# FM349readerV01.net
KiCad netlist of a schematic drawn in Altium Designer
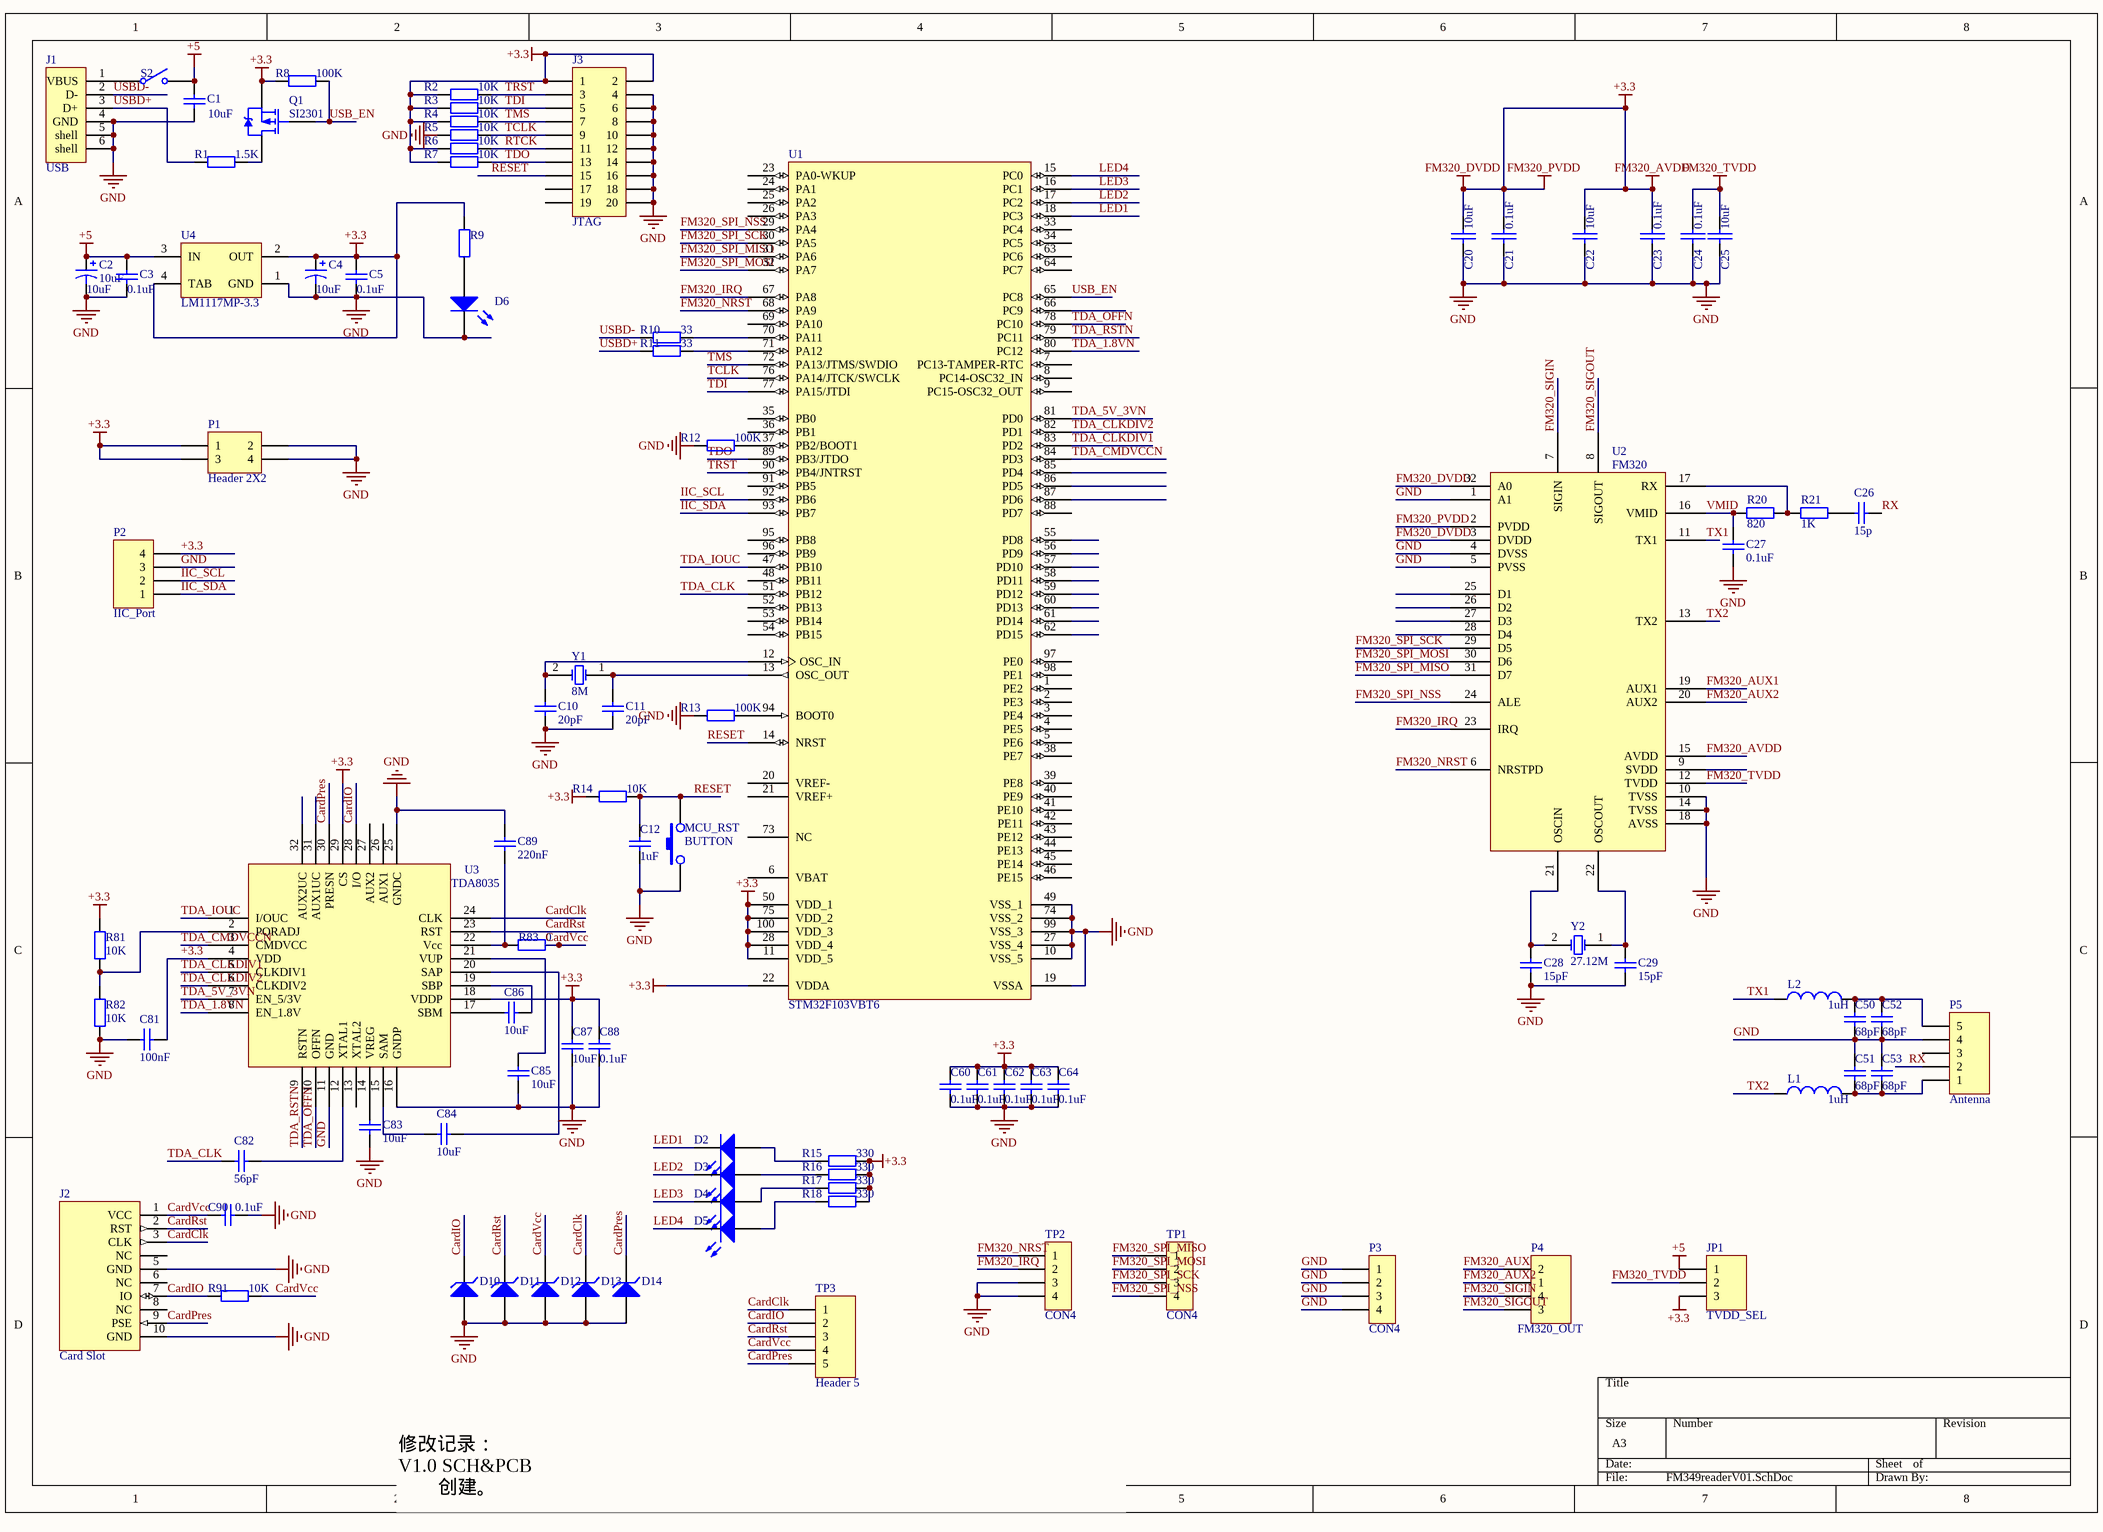
[diagram p0: FM349readerV01.SchDoc]

(export (version "E")
  (design (tool "Eeschema 10.0.6"))
  (components
    (comp (ref "C1")
      (value "10uF")
      (footprint "0805")
      (description "Capacitor")
      (libsource (lib "Miscellaneous Devices") (part "Cap"))
    )
    (comp (ref "C2")
      (value "10uF")
      (footprint "0805")
      (description "Polarized Capacitor (Radial)")
      (fields (field (name "ALTIUM_VALUE") "10uF"))
      (libsource (lib "Miscellaneous Devices") (part "Cap Pol1"))
    )
    (comp (ref "C3")
      (value "0.1uF")
      (footprint "0805")
      (description "Capacitor")
      (libsource (lib "Miscellaneous Devices") (part "Cap"))
    )
    (comp (ref "C4")
      (value "10uF")
      (footprint "0805")
      (description "Polarized Capacitor (Radial)")
      (libsource (lib "Miscellaneous Devices") (part "Cap Pol1"))
    )
    (comp (ref "C5")
      (value "0.1uF")
      (footprint "0805")
      (description "Capacitor")
      (libsource (lib "Miscellaneous Devices") (part "Cap"))
    )
    (comp (ref "C10")
      (value "20pF")
      (footprint "0805")
      (description "Capacitor")
      (libsource (lib "Miscellaneous Devices") (part "Cap"))
    )
    (comp (ref "C11")
      (value "20pF")
      (footprint "0805")
      (description "Capacitor")
      (libsource (lib "Miscellaneous Devices") (part "Cap"))
    )
    (comp (ref "C12")
      (value "1uF")
      (footprint "0805")
      (description "Capacitor")
      (libsource (lib "Miscellaneous Devices") (part "Cap"))
    )
    (comp (ref "C20")
      (value "10uF")
      (footprint "0805")
      (description "Capacitor")
      (libsource (lib "SCH_LIB") (part "CAP"))
    )
    (comp (ref "C21")
      (value "0.1uF")
      (footprint "0805")
      (description "Capacitor")
      (libsource (lib "SCH_LIB") (part "CAP"))
    )
    (comp (ref "C22")
      (value "10uF")
      (footprint "0805")
      (description "Capacitor")
      (libsource (lib "SCH_LIB") (part "CAP"))
    )
    (comp (ref "C23")
      (value "0.1uF")
      (footprint "0805")
      (description "Capacitor")
      (libsource (lib "SCH_LIB") (part "CAP"))
    )
    (comp (ref "C24")
      (value "0.1uF")
      (footprint "0805")
      (description "Capacitor")
      (libsource (lib "SCH_LIB") (part "CAP"))
    )
    (comp (ref "C25")
      (value "10uF")
      (footprint "0805")
      (description "Capacitor")
      (libsource (lib "SCH_LIB") (part "CAP"))
    )
    (comp (ref "C26")
      (value "15p")
      (footprint "0805")
      (description "Capacitor")
      (fields (field (name "Comment") "0.1uF"))
      (libsource (lib "Miscellaneous Devices") (part "Cap"))
    )
    (comp (ref "C27")
      (value "0.1uF")
      (footprint "0805")
      (description "Capacitor")
      (libsource (lib "Miscellaneous Devices") (part "Cap"))
    )
    (comp (ref "C28")
      (value "15pF")
      (footprint "0805")
      (description "Capacitor")
      (libsource (lib "Miscellaneous Devices") (part "Cap"))
    )
    (comp (ref "C29")
      (value "15pF")
      (footprint "0805")
      (description "Capacitor")
      (libsource (lib "Miscellaneous Devices") (part "Cap"))
    )
    (comp (ref "C50")
      (value "68pF")
      (footprint "0805")
      (description "Capacitor")
      (libsource (lib "Miscellaneous Devices") (part "Cap"))
    )
    (comp (ref "C51")
      (value "68pF")
      (footprint "0805")
      (description "Capacitor")
      (libsource (lib "Miscellaneous Devices") (part "Cap"))
    )
    (comp (ref "C52")
      (value "68pF")
      (footprint "0805")
      (description "Capacitor")
      (libsource (lib "Miscellaneous Devices") (part "Cap"))
    )
    (comp (ref "C53")
      (value "68pF")
      (footprint "0805")
      (description "Capacitor")
      (libsource (lib "Miscellaneous Devices") (part "Cap"))
    )
    (comp (ref "C60")
      (value "0.1uF")
      (footprint "0805")
      (description "Capacitor")
      (libsource (lib "Miscellaneous Devices") (part "Cap"))
    )
    (comp (ref "C61")
      (value "0.1uF")
      (footprint "0805")
      (description "Capacitor")
      (libsource (lib "Miscellaneous Devices") (part "Cap"))
    )
    (comp (ref "C62")
      (value "0.1uF")
      (footprint "0805")
      (description "Capacitor")
      (libsource (lib "Miscellaneous Devices") (part "Cap"))
    )
    (comp (ref "C63")
      (value "0.1uF")
      (footprint "0805")
      (description "Capacitor")
      (libsource (lib "Miscellaneous Devices") (part "Cap"))
    )
    (comp (ref "C64")
      (value "0.1uF")
      (footprint "0805")
      (description "Capacitor")
      (libsource (lib "Miscellaneous Devices") (part "Cap"))
    )
    (comp (ref "C81")
      (value "100nF")
      (footprint "0805")
      (description "Capacitor")
      (fields (field (name "Comment") "0.1uF"))
      (libsource (lib "Miscellaneous Devices") (part "Cap"))
    )
    (comp (ref "C82")
      (value "56pF")
      (footprint "0805")
      (description "Capacitor")
      (fields (field (name "Comment") "0.1uF"))
      (libsource (lib "Miscellaneous Devices") (part "Cap"))
    )
    (comp (ref "C83")
      (value "10uF")
      (footprint "0805")
      (description "Capacitor")
      (fields (field (name "Comment") "0.1uF"))
      (libsource (lib "Miscellaneous Devices") (part "Cap"))
    )
    (comp (ref "C84")
      (value "10uF")
      (footprint "0805")
      (description "Capacitor")
      (fields (field (name "Comment") "0.1uF"))
      (libsource (lib "Miscellaneous Devices") (part "Cap"))
    )
    (comp (ref "C85")
      (value "10uF")
      (footprint "0805")
      (description "Capacitor")
      (fields (field (name "Comment") "0.1uF"))
      (libsource (lib "Miscellaneous Devices") (part "Cap"))
    )
    (comp (ref "C86")
      (value "10uF")
      (footprint "0805")
      (description "Capacitor")
      (fields (field (name "Comment") "0.1uF"))
      (libsource (lib "Miscellaneous Devices") (part "Cap"))
    )
    (comp (ref "C87")
      (value "10uF")
      (footprint "0805")
      (description "Capacitor")
      (fields (field (name "Comment") "0.1uF"))
      (libsource (lib "Miscellaneous Devices") (part "Cap"))
    )
    (comp (ref "C88")
      (value "0.1uF")
      (footprint "0805")
      (description "Capacitor")
      (libsource (lib "Miscellaneous Devices") (part "Cap"))
    )
    (comp (ref "C89")
      (value "220nF")
      (footprint "0805")
      (description "Capacitor")
      (fields (field (name "Comment") "0.1uF"))
      (libsource (lib "Miscellaneous Devices") (part "Cap"))
    )
    (comp (ref "C90")
      (value "0.1uF")
      (footprint "0805")
      (description "Capacitor")
      (libsource (lib "Miscellaneous Devices") (part "Cap"))
    )
    (comp (ref "D2")
      (value "LED2")
      (footprint "3.2X1.6X1.1")
      (description "Typical RED, GREEN, YELLOW, AMBER GaAs LED")
      (libsource (lib "Miscellaneous Devices") (part "LED2"))
    )
    (comp (ref "D3")
      (value "LED2")
      (footprint "3.2X1.6X1.1")
      (description "Typical RED, GREEN, YELLOW, AMBER GaAs LED")
      (libsource (lib "Miscellaneous Devices") (part "LED2"))
    )
    (comp (ref "D4")
      (value "LED2")
      (footprint "3.2X1.6X1.1")
      (description "Typical RED, GREEN, YELLOW, AMBER GaAs LED")
      (libsource (lib "Miscellaneous Devices") (part "LED2"))
    )
    (comp (ref "D5")
      (value "LED2")
      (footprint "3.2X1.6X1.1")
      (description "Typical RED, GREEN, YELLOW, AMBER GaAs LED")
      (libsource (lib "Miscellaneous Devices") (part "LED2"))
    )
    (comp (ref "D6")
      (value "LED2")
      (footprint "3.2X1.6X1.1")
      (description "Typical RED, GREEN, YELLOW, AMBER GaAs LED")
      (libsource (lib "Miscellaneous Devices") (part "LED2"))
    )
    (comp (ref "D10")
      (value "ESD")
      (footprint "SOD-323")
      (description "Zener Diode")
      (libsource (lib "Miscellaneous Devices") (part "D Zener"))
    )
    (comp (ref "D11")
      (value "ESD")
      (footprint "SOD-323")
      (description "Zener Diode")
      (libsource (lib "Miscellaneous Devices") (part "D Zener"))
    )
    (comp (ref "D12")
      (value "ESD")
      (footprint "SOD-323")
      (description "Zener Diode")
      (libsource (lib "Miscellaneous Devices") (part "D Zener"))
    )
    (comp (ref "D13")
      (value "ESD")
      (footprint "SOD-323")
      (description "Zener Diode")
      (libsource (lib "Miscellaneous Devices") (part "D Zener"))
    )
    (comp (ref "D14")
      (value "ESD")
      (footprint "SOD-323")
      (description "Zener Diode")
      (libsource (lib "Miscellaneous Devices") (part "D Zener"))
    )
    (comp (ref "J1") (value "USB") (footprint "USB-B") (libsource (lib "USB") (part "USB")))
    (comp (ref "J2")
      (value "Card Slot")
      (footprint "BIG-CARD-SLOT")
      (libsource (lib "fm274") (part "Card Slot"))
    )
    (comp (ref "J3")
      (value "JTAG")
      (footprint "HDR2X10")
      (description "Header, 10-Pin, Dual row")
      (libsource (lib "Miscellaneous Connectors") (part "Header 10X2"))
    )
    (comp (ref "JP1")
      (value "TVDD_SEL")
      (footprint "HDR1X3")
      (description "Header, 3-Pin")
      (libsource (lib "Miscellaneous Connectors") (part "Header 3"))
    )
    (comp (ref "L1")
      (value "1uH")
      (footprint "1812")
      (description "Inductor")
      (libsource (lib "Miscellaneous Devices") (part "Inductor"))
    )
    (comp (ref "L2")
      (value "1uH")
      (footprint "1812")
      (description "Inductor")
      (libsource (lib "Miscellaneous Devices") (part "Inductor"))
    )
    (comp (ref "MCU_RST")
      (value "BUTTON")
      (footprint "BUTTON-S")
      (description "乒乓球按键（压下后接通，松开自动断开），较大按键尺寸12mmX12mm选用BUTTON-L封装，较小尺寸6mmX6mm选用BUTTON-S封装")
      (libsource (lib "fm274") (part "BUTTON"))
    )
    (comp (ref "P1")
      (value "Header 2X2")
      (footprint "HDR2X2")
      (description "Header, 2-Pin, Dual row")
      (libsource (lib "Miscellaneous Connectors") (part "Header 2X2"))
    )
    (comp (ref "P2")
      (value "IIC_Port")
      (footprint "HDR1X4")
      (description "Header, 4-Pin")
      (libsource (lib "Miscellaneous Connectors") (part "Header 4"))
    )
    (comp (ref "P3")
      (value "CON4")
      (footprint "HDR1X4")
      (description "Connector")
      (libsource (lib "YPF") (part "CON4"))
    )
    (comp (ref "P4")
      (value "FM320_OUT")
      (footprint "HDR1X4")
      (description "Header, 4-Pin")
      (libsource (lib "") (part "Header 4_1"))
    )
    (comp (ref "P5")
      (value "Antenna")
      (footprint "HDR1X5")
      (description "Header, 5-Pin")
      (libsource (lib "") (part "Header 5_1"))
    )
    (comp (ref "Q1")
      (value "SI2301")
      (footprint "SOT-23-2301")
      (description "P-Channel Power MOSFET")
      (libsource (lib "Miscellaneous Devices") (part "PMOS-2"))
    )
    (comp (ref "R1")
      (value "1.5K")
      (footprint "0805")
      (description "Resistor")
      (libsource (lib "Miscellaneous Devices") (part "Res2"))
    )
    (comp (ref "R2")
      (value "10K")
      (footprint "0805")
      (description "Resistor")
      (libsource (lib "Miscellaneous Devices") (part "Res2"))
    )
    (comp (ref "R3")
      (value "10K")
      (footprint "0805")
      (description "Resistor")
      (libsource (lib "Miscellaneous Devices") (part "Res2"))
    )
    (comp (ref "R4")
      (value "10K")
      (footprint "0805")
      (description "Resistor")
      (libsource (lib "Miscellaneous Devices") (part "Res2"))
    )
    (comp (ref "R5")
      (value "10K")
      (footprint "0805")
      (description "Resistor")
      (libsource (lib "") (part "Res2_2"))
    )
    (comp (ref "R6")
      (value "10K")
      (footprint "0805")
      (description "Resistor")
      (libsource (lib "Miscellaneous Devices") (part "Res2"))
    )
    (comp (ref "R7")
      (value "10K")
      (footprint "0805")
      (description "Resistor")
      (libsource (lib "Miscellaneous Devices") (part "Res2"))
    )
    (comp (ref "R8")
      (value "100K")
      (footprint "0805")
      (description "Resistor")
      (fields (field (name "Comment") "10K"))
      (libsource (lib "Miscellaneous Devices") (part "Res2"))
    )
    (comp (ref "R9")
      (value "1.5K")
      (footprint "0805")
      (description "Resistor")
      (libsource (lib "") (part "Res2_1"))
    )
    (comp (ref "R10")
      (value "33")
      (footprint "0805")
      (description "Resistor")
      (libsource (lib "Miscellaneous Devices") (part "Res2"))
    )
    (comp (ref "R11")
      (value "33")
      (footprint "0805")
      (description "Resistor")
      (libsource (lib "Miscellaneous Devices") (part "Res2"))
    )
    (comp (ref "R12")
      (value "100K")
      (footprint "0805")
      (description "Resistor")
      (libsource (lib "Miscellaneous Devices") (part "Res2"))
    )
    (comp (ref "R13")
      (value "100K")
      (footprint "0805")
      (description "Resistor")
      (libsource (lib "Miscellaneous Devices") (part "Res2"))
    )
    (comp (ref "R14")
      (value "10K")
      (footprint "0805")
      (description "Resistor")
      (libsource (lib "Miscellaneous Devices") (part "Res2"))
    )
    (comp (ref "R15")
      (value "330")
      (footprint "0805")
      (description "Resistor")
      (libsource (lib "Miscellaneous Devices") (part "Res2"))
    )
    (comp (ref "R16")
      (value "330")
      (footprint "0805")
      (description "Resistor")
      (libsource (lib "") (part "Res2_2"))
    )
    (comp (ref "R17")
      (value "330")
      (footprint "0805")
      (description "Resistor")
      (libsource (lib "Miscellaneous Devices") (part "Res2"))
    )
    (comp (ref "R18")
      (value "330")
      (footprint "0805")
      (description "Resistor")
      (libsource (lib "Miscellaneous Devices") (part "Res2"))
    )
    (comp (ref "R20")
      (value "820")
      (footprint "0805")
      (description "Resistor")
      (libsource (lib "") (part "Res2_2"))
    )
    (comp (ref "R21")
      (value "1K")
      (footprint "0805")
      (description "Resistor")
      (libsource (lib "") (part "Res2_2"))
    )
    (comp (ref "R81")
      (value "10K")
      (footprint "0805")
      (description "Resistor")
      (fields (field (name "Comment") "1.5K"))
      (libsource (lib "") (part "Res2_1"))
    )
    (comp (ref "R82")
      (value "10K")
      (footprint "0805")
      (description "Resistor")
      (fields (field (name "Comment") "1.5K"))
      (libsource (lib "") (part "Res2_1"))
    )
    (comp (ref "R83")
      (value "0")
      (footprint "0805")
      (description "Resistor")
      (fields (field (name "Comment") "10K"))
      (libsource (lib "Miscellaneous Devices") (part "Res2"))
    )
    (comp (ref "R91")
      (value "10K")
      (footprint "0805")
      (description "Resistor")
      (fields (field (name "Comment") "1.5K"))
      (libsource (lib "Miscellaneous Devices") (part "Res2"))
    )
    (comp (ref "S2")
      (value "SW-SPST")
      (footprint "SW")
      (description "Single-Pole, Single-Throw Switch")
      (libsource (lib "Miscellaneous Devices") (part "SW-SPST"))
    )
    (comp (ref "TP1")
      (value "CON4")
      (footprint "HDR1X4")
      (description "Connector")
      (libsource (lib "YPF") (part "CON4"))
    )
    (comp (ref "TP2")
      (value "CON4")
      (footprint "HDR1X4")
      (description "Connector")
      (libsource (lib "YPF") (part "CON4"))
    )
    (comp (ref "TP3")
      (value "Header 5")
      (footprint "HDR1X5")
      (description "Header, 5-Pin")
      (libsource (lib "Miscellaneous Connectors") (part "Header 5"))
    )
    (comp (ref "U1")
      (value "STM32F103VBT6")
      (footprint "LQFP100_L")
      (description "STM32 ARM-based 32-bit MCU with 64 Kbytes Flash, 100-pin LQFP, Industrial Temperature")
      (libsource (lib "ST Microcontroller 32-Bit STM32") (part "STM32F103VBT6"))
    )
    (comp (ref "U2")
      (value "FM320")
      (footprint "FM320_PIN32")
      (libsource (lib "SmartCardReader") (part "PN5120A0HN1"))
    )
    (comp (ref "U3")
      (value "TDA8035")
      (footprint "TDA8035_PIN32")
      (libsource (lib "SmartCardReader") (part "TDA8035"))
    )
    (comp (ref "U4")
      (value "LM1117MP-3.3")
      (footprint "MP04A_L")
      (description "800mA Low-Dropout Linear Regulator")
      (fields
        (field (name "MANUFACTURER") "National Semiconductor")
        (field (name "DIGIKEYPARTNUMBER") "LM1117MP-3.3CT-ND")
      )
      (libsource (lib "NSC LDO") (part "LM1117MP-3.3"))
    )
    (comp (ref "Y1")
      (value "8M")
      (footprint "XTAL-0.2")
      (description "Crystal Oscillator")
      (libsource (lib "Miscellaneous Devices") (part "XTAL"))
    )
    (comp (ref "Y2")
      (value "27.12M")
      (footprint "XTAL-0.2")
      (description "Crystal Oscillator")
      (libsource (lib "Miscellaneous Devices") (part "XTAL"))
    )
  )
  (nets
    (net (code "1") (name "+3.3") (class "Default")
      (node (ref "C20") (pin "2") (pinfunction "2_2") (pintype "passive"))
      (node (ref "C21") (pin "1") (pinfunction "1_1") (pintype "passive"))
      (node (ref "C22") (pin "1") (pinfunction "1_1") (pintype "passive"))
      (node (ref "C23") (pin "1") (pinfunction "1_1") (pintype "passive"))
      (node (ref "C4") (pin "1") (pinfunction "1_1") (pintype "passive"))
      (node (ref "C5") (pin "2") (pinfunction "2_2") (pintype "passive"))
      (node (ref "C60") (pin "2") (pinfunction "2_2") (pintype "passive"))
      (node (ref "C61") (pin "2") (pinfunction "2_2") (pintype "passive"))
      (node (ref "C62") (pin "2") (pinfunction "2_2") (pintype "passive"))
      (node (ref "C63") (pin "2") (pinfunction "2_2") (pintype "passive"))
      (node (ref "C64") (pin "2") (pinfunction "2_2") (pintype "passive"))
      (node (ref "C81") (pin "1") (pinfunction "1_1") (pintype "passive"))
      (node (ref "C87") (pin "2") (pinfunction "2_2") (pintype "passive"))
      (node (ref "C88") (pin "2") (pinfunction "2_2") (pintype "passive"))
      (node (ref "J3") (pin "1") (pinfunction "1_1") (pintype "passive"))
      (node (ref "J3") (pin "2") (pinfunction "2_2") (pintype "passive"))
      (node (ref "JP1") (pin "3") (pinfunction "3_3") (pintype "passive"))
      (node (ref "P1") (pin "1") (pinfunction "1_1") (pintype "passive"))
      (node (ref "P1") (pin "3") (pinfunction "3_3") (pintype "passive"))
      (node (ref "P2") (pin "4") (pinfunction "4_4") (pintype "passive"))
      (node (ref "Q1") (pin "3") (pinfunction "S_3") (pintype "passive"))
      (node (ref "R14") (pin "1") (pinfunction "1_1") (pintype "passive"))
      (node (ref "R15") (pin "2") (pinfunction "2_2") (pintype "passive"))
      (node (ref "R16") (pin "1") (pinfunction "1_1") (pintype "passive"))
      (node (ref "R17") (pin "2") (pinfunction "2_2") (pintype "passive"))
      (node (ref "R18") (pin "2") (pinfunction "2_2") (pintype "passive"))
      (node (ref "R2") (pin "1") (pinfunction "1_1") (pintype "passive"))
      (node (ref "R3") (pin "1") (pinfunction "1_1") (pintype "passive"))
      (node (ref "R4") (pin "1") (pinfunction "1_1") (pintype "passive"))
      (node (ref "R6") (pin "1") (pinfunction "1_1") (pintype "passive"))
      (node (ref "R7") (pin "1") (pinfunction "1_1") (pintype "passive"))
      (node (ref "R8") (pin "1") (pinfunction "1_1") (pintype "passive"))
      (node (ref "R81") (pin "2") (pinfunction "2_2") (pintype "passive"))
      (node (ref "R9") (pin "2") (pinfunction "2_2") (pintype "passive"))
      (node (ref "U1") (pin "100") (pinfunction "VDD_3_100") (pintype "power_in"))
      (node (ref "U1") (pin "11") (pinfunction "VDD_5_11") (pintype "power_in"))
      (node (ref "U1") (pin "22") (pinfunction "VDDA_22") (pintype "power_in"))
      (node (ref "U1") (pin "28") (pinfunction "VDD_4_28") (pintype "power_in"))
      (node (ref "U1") (pin "50") (pinfunction "VDD_1_50") (pintype "power_in"))
      (node (ref "U1") (pin "75") (pinfunction "VDD_2_75") (pintype "power_in"))
      (node (ref "U2") (pin "15") (pinfunction "AVDD_15") (pintype "passive"))
      (node (ref "U2") (pin "2") (pinfunction "PVDD_2") (pintype "passive"))
      (node (ref "U2") (pin "3") (pinfunction "DVDD_3") (pintype "passive"))
      (node (ref "U2") (pin "32") (pinfunction "A0_32") (pintype "passive"))
      (node (ref "U3") (pin "18") (pinfunction "VDDP_18") (pintype "passive"))
      (node (ref "U3") (pin "29") (pinfunction "CS_29") (pintype "passive"))
      (node (ref "U3") (pin "4") (pinfunction "VDD_4") (pintype "passive"))
      (node (ref "U4") (pin "2") (pinfunction "OUT_2") (pintype "power_in"))
      (node (ref "U4") (pin "4") (pinfunction "TAB_4") (pintype "power_in"))
    )
    (net (code "2") (name "+5") (class "Default")
      (node (ref "C1") (pin "2") (pinfunction "2_2") (pintype "passive"))
      (node (ref "C2") (pin "1") (pinfunction "1_1") (pintype "passive"))
      (node (ref "C3") (pin "2") (pinfunction "2_2") (pintype "passive"))
      (node (ref "JP1") (pin "1") (pinfunction "1_1") (pintype "passive"))
      (node (ref "S2") (pin "2") (pinfunction "NO_2") (pintype "passive"))
      (node (ref "U4") (pin "3") (pinfunction "IN_3") (pintype "power_in"))
    )
    (net (code "3") (name "/CardClk") (class "Default")
      (node (ref "D13") (pin "2") (pinfunction "K_2") (pintype "passive"))
      (node (ref "J2") (pin "3") (pinfunction "CLK_3") (pintype "output"))
      (node (ref "TP3") (pin "1") (pinfunction "1_1") (pintype "passive"))
      (node (ref "U3") (pin "24") (pinfunction "CLK_24") (pintype "passive"))
    )
    (net (code "4") (name "/CardIO") (class "Default")
      (node (ref "D10") (pin "2") (pinfunction "K_2") (pintype "passive"))
      (node (ref "J2") (pin "7") (pinfunction "IO_7") (pintype "bidirectional"))
      (node (ref "R91") (pin "1") (pinfunction "1_1") (pintype "passive"))
      (node (ref "TP3") (pin "2") (pinfunction "2_2") (pintype "passive"))
      (node (ref "U3") (pin "28") (pinfunction "I/O_28") (pintype "passive"))
    )
    (net (code "5") (name "/CardPres") (class "Default")
      (node (ref "D14") (pin "2") (pinfunction "K_2") (pintype "passive"))
      (node (ref "J2") (pin "9") (pinfunction "PSE_9") (pintype "input"))
      (node (ref "TP3") (pin "5") (pinfunction "5_5") (pintype "passive"))
      (node (ref "U3") (pin "30") (pinfunction "PRESN_30") (pintype "passive"))
    )
    (net (code "6") (name "/CardRst") (class "Default")
      (node (ref "D11") (pin "2") (pinfunction "K_2") (pintype "passive"))
      (node (ref "J2") (pin "2") (pinfunction "RST_2") (pintype "output"))
      (node (ref "TP3") (pin "3") (pinfunction "3_3") (pintype "passive"))
      (node (ref "U3") (pin "23") (pinfunction "RST_23") (pintype "passive"))
    )
    (net (code "7") (name "/CardVcc") (class "Default")
      (node (ref "C90") (pin "1") (pinfunction "1_1") (pintype "passive"))
      (node (ref "D12") (pin "2") (pinfunction "K_2") (pintype "passive"))
      (node (ref "J2") (pin "1") (pinfunction "VCC_1") (pintype "power_in"))
      (node (ref "R83") (pin "2") (pinfunction "2_2") (pintype "passive"))
      (node (ref "R91") (pin "2") (pinfunction "2_2") (pintype "passive"))
      (node (ref "TP3") (pin "4") (pinfunction "4_4") (pintype "passive"))
    )
    (net (code "8") (name "/FM320_AUX1") (class "Default")
      (node (ref "P4") (pin "2") (pinfunction "2_2") (pintype "passive"))
      (node (ref "U2") (pin "19") (pinfunction "AUX1_19") (pintype "passive"))
    )
    (net (code "9") (name "/FM320_AUX2") (class "Default")
      (node (ref "P4") (pin "1") (pinfunction "1_1") (pintype "passive"))
      (node (ref "U2") (pin "20") (pinfunction "AUX2_20") (pintype "passive"))
    )
    (net (code "10") (name "/FM320_IRQ") (class "Default")
      (node (ref "TP2") (pin "2") (pinfunction "2_2") (pintype "passive"))
      (node (ref "U1") (pin "67") (pinfunction "PA8_67") (pintype "bidirectional"))
      (node (ref "U2") (pin "23") (pinfunction "IRQ_23") (pintype "passive"))
    )
    (net (code "11") (name "/FM320_NRST") (class "Default")
      (node (ref "TP2") (pin "1") (pinfunction "1_1") (pintype "passive"))
      (node (ref "U1") (pin "68") (pinfunction "PA9_68") (pintype "bidirectional"))
      (node (ref "U2") (pin "6") (pinfunction "NRSTPD_6") (pintype "passive"))
    )
    (net (code "12") (name "/FM320_SIGIN") (class "Default")
      (node (ref "P4") (pin "4") (pinfunction "4_4") (pintype "passive"))
      (node (ref "U2") (pin "7") (pinfunction "SIGIN_7") (pintype "passive"))
    )
    (net (code "13") (name "/FM320_SIGOUT") (class "Default")
      (node (ref "P4") (pin "3") (pinfunction "3_3") (pintype "passive"))
      (node (ref "U2") (pin "8") (pinfunction "SIGOUT_8") (pintype "passive"))
    )
    (net (code "14") (name "/FM320_SPI_MISO") (class "Default")
      (node (ref "TP1") (pin "1") (pinfunction "1_1") (pintype "passive"))
      (node (ref "U1") (pin "31") (pinfunction "PA6_31") (pintype "bidirectional"))
      (node (ref "U2") (pin "31") (pinfunction "D7_31") (pintype "passive"))
    )
    (net (code "15") (name "/FM320_SPI_MOSI") (class "Default")
      (node (ref "TP1") (pin "2") (pinfunction "2_2") (pintype "passive"))
      (node (ref "U1") (pin "32") (pinfunction "PA7_32") (pintype "bidirectional"))
      (node (ref "U2") (pin "30") (pinfunction "D6_30") (pintype "passive"))
    )
    (net (code "16") (name "/FM320_SPI_NSS") (class "Default")
      (node (ref "TP1") (pin "4") (pinfunction "4_4") (pintype "passive"))
      (node (ref "U1") (pin "29") (pinfunction "PA4_29") (pintype "bidirectional"))
      (node (ref "U2") (pin "24") (pinfunction "ALE_24") (pintype "passive"))
    )
    (net (code "17") (name "/FM320_SPI_SCK") (class "Default")
      (node (ref "TP1") (pin "3") (pinfunction "3_3") (pintype "passive"))
      (node (ref "U1") (pin "30") (pinfunction "PA5_30") (pintype "bidirectional"))
      (node (ref "U2") (pin "29") (pinfunction "D5_29") (pintype "passive"))
    )
    (net (code "18") (name "/IIC_SCL") (class "Default")
      (node (ref "P2") (pin "2") (pinfunction "2_2") (pintype "passive"))
      (node (ref "U1") (pin "92") (pinfunction "PB6_92") (pintype "bidirectional"))
    )
    (net (code "19") (name "/IIC_SDA") (class "Default")
      (node (ref "P2") (pin "1") (pinfunction "1_1") (pintype "passive"))
      (node (ref "U1") (pin "93") (pinfunction "PB7_93") (pintype "bidirectional"))
    )
    (net (code "20") (name "/LED1") (class "Default")
      (node (ref "D2") (pin "2") (pinfunction "K_2") (pintype "passive"))
      (node (ref "U1") (pin "18") (pinfunction "PC3_18") (pintype "bidirectional"))
    )
    (net (code "21") (name "/LED2") (class "Default")
      (node (ref "D3") (pin "2") (pinfunction "K_2") (pintype "passive"))
      (node (ref "U1") (pin "17") (pinfunction "PC2_17") (pintype "bidirectional"))
    )
    (net (code "22") (name "/LED3") (class "Default")
      (node (ref "D4") (pin "2") (pinfunction "K_2") (pintype "passive"))
      (node (ref "U1") (pin "16") (pinfunction "PC1_16") (pintype "bidirectional"))
    )
    (net (code "23") (name "/LED4") (class "Default")
      (node (ref "D5") (pin "2") (pinfunction "K_2") (pintype "passive"))
      (node (ref "U1") (pin "15") (pinfunction "PC0_15") (pintype "bidirectional"))
    )
    (net (code "24") (name "/RESET") (class "Default")
      (node (ref "C12") (pin "2") (pinfunction "2_2") (pintype "passive"))
      (node (ref "J3") (pin "15") (pinfunction "15_15") (pintype "passive"))
      (node (ref "MCU_RST") (pin "2") (pinfunction "2_2") (pintype "passive"))
      (node (ref "R14") (pin "2") (pinfunction "2_2") (pintype "passive"))
      (node (ref "U1") (pin "14") (pinfunction "NRST_14") (pintype "bidirectional"))
    )
    (net (code "25") (name "/RTCK") (class "Default")
      (node (ref "J3") (pin "11") (pinfunction "11_11") (pintype "passive"))
      (node (ref "R6") (pin "2") (pinfunction "2_2") (pintype "passive"))
    )
    (net (code "26") (name "/RX") (class "Default")
      (node (ref "C26") (pin "1") (pinfunction "1_1") (pintype "passive"))
      (node (ref "P5") (pin "2") (pinfunction "2_2") (pintype "passive"))
    )
    (net (code "27") (name "/TCLK") (class "Default")
      (node (ref "J3") (pin "9") (pinfunction "9_9") (pintype "passive"))
      (node (ref "R5") (pin "1") (pinfunction "1_1") (pintype "passive"))
      (node (ref "U1") (pin "76") (pinfunction "PA14/JTCK/SWCLK_76") (pintype "bidirectional"))
    )
    (net (code "28") (name "/TDA_1.8VN") (class "Default")
      (node (ref "U1") (pin "80") (pinfunction "PC12_80") (pintype "bidirectional"))
      (node (ref "U3") (pin "8") (pinfunction "EN_1.8V_8") (pintype "passive"))
    )
    (net (code "29") (name "/TDA_5V_3VN") (class "Default")
      (node (ref "U1") (pin "81") (pinfunction "PD0_81") (pintype "bidirectional"))
      (node (ref "U3") (pin "7") (pinfunction "EN_5/3V_7") (pintype "passive"))
    )
    (net (code "30") (name "/TDA_CLK") (class "Default")
      (node (ref "C82") (pin "1") (pinfunction "1_1") (pintype "passive"))
      (node (ref "U1") (pin "51") (pinfunction "PB12_51") (pintype "bidirectional"))
    )
    (net (code "31") (name "/TDA_CLKDIV1") (class "Default")
      (node (ref "U1") (pin "83") (pinfunction "PD2_83") (pintype "bidirectional"))
      (node (ref "U3") (pin "5") (pinfunction "CLKDIV1_5") (pintype "passive"))
    )
    (net (code "32") (name "/TDA_CLKDIV2") (class "Default")
      (node (ref "U1") (pin "82") (pinfunction "PD1_82") (pintype "bidirectional"))
      (node (ref "U3") (pin "6") (pinfunction "CLKDIV2_6") (pintype "passive"))
    )
    (net (code "33") (name "/TDA_CMDVCCN") (class "Default")
      (node (ref "U1") (pin "84") (pinfunction "PD3_84") (pintype "bidirectional"))
      (node (ref "U3") (pin "3") (pinfunction "CMDVCC_3") (pintype "passive"))
    )
    (net (code "34") (name "/TDA_IOUC") (class "Default")
      (node (ref "U1") (pin "47") (pinfunction "PB10_47") (pintype "bidirectional"))
      (node (ref "U3") (pin "1") (pinfunction "I/OUC_1") (pintype "passive"))
    )
    (net (code "35") (name "/TDA_OFFN") (class "Default")
      (node (ref "U1") (pin "78") (pinfunction "PC10_78") (pintype "bidirectional"))
      (node (ref "U3") (pin "10") (pinfunction "OFFN_10") (pintype "passive"))
    )
    (net (code "36") (name "/TDA_RSTN") (class "Default")
      (node (ref "U1") (pin "79") (pinfunction "PC11_79") (pintype "bidirectional"))
      (node (ref "U3") (pin "9") (pinfunction "RSTN_9") (pintype "passive"))
    )
    (net (code "37") (name "/TDI") (class "Default")
      (node (ref "J3") (pin "5") (pinfunction "5_5") (pintype "passive"))
      (node (ref "R3") (pin "2") (pinfunction "2_2") (pintype "passive"))
      (node (ref "U1") (pin "77") (pinfunction "PA15/JTDI_77") (pintype "bidirectional"))
    )
    (net (code "38") (name "/TDO") (class "Default")
      (node (ref "J3") (pin "13") (pinfunction "13_13") (pintype "passive"))
      (node (ref "R7") (pin "2") (pinfunction "2_2") (pintype "passive"))
      (node (ref "U1") (pin "89") (pinfunction "PB3/JTDO_89") (pintype "bidirectional"))
    )
    (net (code "39") (name "/TMS") (class "Default")
      (node (ref "J3") (pin "7") (pinfunction "7_7") (pintype "passive"))
      (node (ref "R4") (pin "2") (pinfunction "2_2") (pintype "passive"))
      (node (ref "U1") (pin "72") (pinfunction "PA13/JTMS/SWDIO_72") (pintype "bidirectional"))
    )
    (net (code "40") (name "/TRST") (class "Default")
      (node (ref "J3") (pin "3") (pinfunction "3_3") (pintype "passive"))
      (node (ref "R2") (pin "2") (pinfunction "2_2") (pintype "passive"))
      (node (ref "U1") (pin "90") (pinfunction "PB4/JNTRST_90") (pintype "bidirectional"))
    )
    (net (code "41") (name "/TX1") (class "Default")
      (node (ref "L2") (pin "1") (pinfunction "1_1") (pintype "passive"))
      (node (ref "U2") (pin "11") (pinfunction "TX1_11") (pintype "passive"))
    )
    (net (code "42") (name "/TX2") (class "Default")
      (node (ref "L1") (pin "1") (pinfunction "1_1") (pintype "passive"))
      (node (ref "U2") (pin "13") (pinfunction "TX2_13") (pintype "passive"))
    )
    (net (code "43") (name "/USBD+") (class "Default")
      (node (ref "J1") (pin "3") (pinfunction "D+_3") (pintype "passive"))
      (node (ref "R1") (pin "1") (pinfunction "1_1") (pintype "passive"))
      (node (ref "R11") (pin "1") (pinfunction "1_1") (pintype "passive"))
    )
    (net (code "44") (name "/USBD-") (class "Default")
      (node (ref "J1") (pin "2") (pinfunction "D-_2") (pintype "passive"))
      (node (ref "R10") (pin "1") (pinfunction "1_1") (pintype "passive"))
    )
    (net (code "45") (name "/USB_EN") (class "Default")
      (node (ref "Q1") (pin "1") (pinfunction "G_1") (pintype "passive"))
      (node (ref "R8") (pin "2") (pinfunction "2_2") (pintype "passive"))
      (node (ref "U1") (pin "65") (pinfunction "PC8_65") (pintype "bidirectional"))
    )
    (net (code "46") (name "/VMID") (class "Default")
      (node (ref "C27") (pin "1") (pinfunction "1_1") (pintype "passive"))
      (node (ref "R20") (pin "2") (pinfunction "2_2") (pintype "passive"))
      (node (ref "U2") (pin "16") (pinfunction "VMID_16") (pintype "passive"))
    )
    (net (code "47") (name "FM320_TVDD") (class "Default")
      (node (ref "C24") (pin "1") (pinfunction "1_1") (pintype "passive"))
      (node (ref "C25") (pin "1") (pinfunction "1_1") (pintype "passive"))
      (node (ref "JP1") (pin "2") (pinfunction "2_2") (pintype "passive"))
      (node (ref "U2") (pin "12") (pinfunction "TVDD_12") (pintype "passive"))
    )
    (net (code "48") (name "GND") (class "Default")
      (node (ref "C1") (pin "1") (pinfunction "1_1") (pintype "passive"))
      (node (ref "C10") (pin "1") (pinfunction "1_1") (pintype "passive"))
      (node (ref "C11") (pin "1") (pinfunction "1_1") (pintype "passive"))
      (node (ref "C12") (pin "1") (pinfunction "1_1") (pintype "passive"))
      (node (ref "C2") (pin "2") (pinfunction "2_2") (pintype "passive"))
      (node (ref "C20") (pin "1") (pinfunction "1_1") (pintype "passive"))
      (node (ref "C21") (pin "2") (pinfunction "2_2") (pintype "passive"))
      (node (ref "C22") (pin "2") (pinfunction "2_2") (pintype "passive"))
      (node (ref "C23") (pin "2") (pinfunction "2_2") (pintype "passive"))
      (node (ref "C24") (pin "2") (pinfunction "2_2") (pintype "passive"))
      (node (ref "C25") (pin "2") (pinfunction "2_2") (pintype "passive"))
      (node (ref "C27") (pin "2") (pinfunction "2_2") (pintype "passive"))
      (node (ref "C28") (pin "1") (pinfunction "1_1") (pintype "passive"))
      (node (ref "C29") (pin "1") (pinfunction "1_1") (pintype "passive"))
      (node (ref "C3") (pin "1") (pinfunction "1_1") (pintype "passive"))
      (node (ref "C4") (pin "2") (pinfunction "2_2") (pintype "passive"))
      (node (ref "C5") (pin "1") (pinfunction "1_1") (pintype "passive"))
      (node (ref "C50") (pin "2") (pinfunction "2_2") (pintype "passive"))
      (node (ref "C51") (pin "1") (pinfunction "1_1") (pintype "passive"))
      (node (ref "C52") (pin "2") (pinfunction "2_2") (pintype "passive"))
      (node (ref "C53") (pin "1") (pinfunction "1_1") (pintype "passive"))
      (node (ref "C60") (pin "1") (pinfunction "1_1") (pintype "passive"))
      (node (ref "C61") (pin "1") (pinfunction "1_1") (pintype "passive"))
      (node (ref "C62") (pin "1") (pinfunction "1_1") (pintype "passive"))
      (node (ref "C63") (pin "1") (pinfunction "1_1") (pintype "passive"))
      (node (ref "C64") (pin "1") (pinfunction "1_1") (pintype "passive"))
      (node (ref "C81") (pin "2") (pinfunction "2_2") (pintype "passive"))
      (node (ref "C83") (pin "2") (pinfunction "2_2") (pintype "passive"))
      (node (ref "C85") (pin "1") (pinfunction "1_1") (pintype "passive"))
      (node (ref "C87") (pin "1") (pinfunction "1_1") (pintype "passive"))
      (node (ref "C88") (pin "1") (pinfunction "1_1") (pintype "passive"))
      (node (ref "C89") (pin "1") (pinfunction "1_1") (pintype "passive"))
      (node (ref "C90") (pin "2") (pinfunction "2_2") (pintype "passive"))
      (node (ref "D10") (pin "1") (pinfunction "A_1") (pintype "passive"))
      (node (ref "D11") (pin "1") (pinfunction "A_1") (pintype "passive"))
      (node (ref "D12") (pin "1") (pinfunction "A_1") (pintype "passive"))
      (node (ref "D13") (pin "1") (pinfunction "A_1") (pintype "passive"))
      (node (ref "D14") (pin "1") (pinfunction "A_1") (pintype "passive"))
      (node (ref "D6") (pin "2") (pinfunction "K_2") (pintype "passive"))
      (node (ref "J1") (pin "4") (pinfunction "GND_4") (pintype "passive"))
      (node (ref "J1") (pin "5") (pinfunction "shell_5") (pintype "passive"))
      (node (ref "J1") (pin "6") (pinfunction "shell_6") (pintype "passive"))
      (node (ref "J2") (pin "10") (pinfunction "GND_10") (pintype "power_in"))
      (node (ref "J2") (pin "5") (pinfunction "GND_5") (pintype "power_in"))
      (node (ref "J3") (pin "10") (pinfunction "10_10") (pintype "passive"))
      (node (ref "J3") (pin "12") (pinfunction "12_12") (pintype "passive"))
      (node (ref "J3") (pin "14") (pinfunction "14_14") (pintype "passive"))
      (node (ref "J3") (pin "16") (pinfunction "16_16") (pintype "passive"))
      (node (ref "J3") (pin "18") (pinfunction "18_18") (pintype "passive"))
      (node (ref "J3") (pin "20") (pinfunction "20_20") (pintype "passive"))
      (node (ref "J3") (pin "4") (pinfunction "4_4") (pintype "passive"))
      (node (ref "J3") (pin "6") (pinfunction "6_6") (pintype "passive"))
      (node (ref "J3") (pin "8") (pinfunction "8_8") (pintype "passive"))
      (node (ref "MCU_RST") (pin "1") (pinfunction "1_1") (pintype "passive"))
      (node (ref "P1") (pin "2") (pinfunction "2_2") (pintype "passive"))
      (node (ref "P1") (pin "4") (pinfunction "4_4") (pintype "passive"))
      (node (ref "P2") (pin "3") (pinfunction "3_3") (pintype "passive"))
      (node (ref "P3") (pin "1") (pinfunction "1_1") (pintype "passive"))
      (node (ref "P3") (pin "2") (pinfunction "2_2") (pintype "passive"))
      (node (ref "P3") (pin "3") (pinfunction "3_3") (pintype "passive"))
      (node (ref "P3") (pin "4") (pinfunction "4_4") (pintype "passive"))
      (node (ref "P5") (pin "4") (pinfunction "4_4") (pintype "passive"))
      (node (ref "R12") (pin "1") (pinfunction "1_1") (pintype "passive"))
      (node (ref "R13") (pin "1") (pinfunction "1_1") (pintype "passive"))
      (node (ref "R5") (pin "2") (pinfunction "2_2") (pintype "passive"))
      (node (ref "R82") (pin "1") (pinfunction "1_1") (pintype "passive"))
      (node (ref "TP2") (pin "3") (pinfunction "3_3") (pintype "passive"))
      (node (ref "TP2") (pin "4") (pinfunction "4_4") (pintype "passive"))
      (node (ref "U1") (pin "10") (pinfunction "VSS_5_10") (pintype "power_in"))
      (node (ref "U1") (pin "19") (pinfunction "VSSA_19") (pintype "power_in"))
      (node (ref "U1") (pin "27") (pinfunction "VSS_4_27") (pintype "power_in"))
      (node (ref "U1") (pin "49") (pinfunction "VSS_1_49") (pintype "power_in"))
      (node (ref "U1") (pin "74") (pinfunction "VSS_2_74") (pintype "power_in"))
      (node (ref "U1") (pin "99") (pinfunction "VSS_3_99") (pintype "power_in"))
      (node (ref "U2") (pin "1") (pinfunction "A1_1") (pintype "passive"))
      (node (ref "U2") (pin "10") (pinfunction "TVSS_10") (pintype "passive"))
      (node (ref "U2") (pin "14") (pinfunction "TVSS_14") (pintype "passive"))
      (node (ref "U2") (pin "18") (pinfunction "AVSS_18") (pintype "passive"))
      (node (ref "U2") (pin "4") (pinfunction "DVSS_4") (pintype "passive"))
      (node (ref "U2") (pin "5") (pinfunction "PVSS_5") (pintype "passive"))
      (node (ref "U3") (pin "11") (pinfunction "GND_11") (pintype "passive"))
      (node (ref "U3") (pin "16") (pinfunction "GNDP_16") (pintype "passive"))
      (node (ref "U3") (pin "25") (pinfunction "GNDC_25") (pintype "passive"))
      (node (ref "U4") (pin "1") (pinfunction "GND_1") (pintype "power_in"))
    )
    (net (code "49") (name "Net-(C26-Pad2)") (class "Default")
      (node (ref "C26") (pin "2") (pinfunction "2_2") (pintype "passive"))
      (node (ref "R21") (pin "1") (pinfunction "1_1") (pintype "passive"))
    )
    (net (code "50") (name "Net-(C50-Pad1)") (class "Default")
      (node (ref "C50") (pin "1") (pinfunction "1_1") (pintype "passive"))
      (node (ref "C52") (pin "1") (pinfunction "1_1") (pintype "passive"))
      (node (ref "L2") (pin "2") (pinfunction "2_2") (pintype "passive"))
      (node (ref "P5") (pin "5") (pinfunction "5_5") (pintype "passive"))
    )
    (net (code "51") (name "Net-(C51-Pad2)") (class "Default")
      (node (ref "C51") (pin "2") (pinfunction "2_2") (pintype "passive"))
      (node (ref "C53") (pin "2") (pinfunction "2_2") (pintype "passive"))
      (node (ref "L1") (pin "2") (pinfunction "2_2") (pintype "passive"))
      (node (ref "P5") (pin "1") (pinfunction "1_1") (pintype "passive"))
    )
    (net (code "52") (name "Net-(D2-A)") (class "Default")
      (node (ref "D2") (pin "1") (pinfunction "A_1") (pintype "passive"))
      (node (ref "R15") (pin "1") (pinfunction "1_1") (pintype "passive"))
    )
    (net (code "53") (name "Net-(D3-A)") (class "Default")
      (node (ref "D3") (pin "1") (pinfunction "A_1") (pintype "passive"))
      (node (ref "R16") (pin "2") (pinfunction "2_2") (pintype "passive"))
    )
    (net (code "54") (name "Net-(D4-A)") (class "Default")
      (node (ref "D4") (pin "1") (pinfunction "A_1") (pintype "passive"))
      (node (ref "R17") (pin "1") (pinfunction "1_1") (pintype "passive"))
    )
    (net (code "55") (name "Net-(D5-A)") (class "Default")
      (node (ref "D5") (pin "1") (pinfunction "A_1") (pintype "passive"))
      (node (ref "R18") (pin "1") (pinfunction "1_1") (pintype "passive"))
    )
    (net (code "56") (name "Net-(D6-A)") (class "Default")
      (node (ref "D6") (pin "1") (pinfunction "A_1") (pintype "passive"))
      (node (ref "R9") (pin "1") (pinfunction "1_1") (pintype "passive"))
    )
    (net (code "57") (name "Net-(J1-VBUS)") (class "Default")
      (node (ref "J1") (pin "1") (pinfunction "VBUS_1") (pintype "passive"))
      (node (ref "S2") (pin "1") (pinfunction "COMMON_1") (pintype "passive"))
    )
    (net (code "58") (name "Net-(Q1-D)") (class "Default")
      (node (ref "Q1") (pin "2") (pinfunction "D_2") (pintype "passive"))
      (node (ref "R1") (pin "2") (pinfunction "2_2") (pintype "passive"))
    )
    (net (code "59") (name "Net-(U1-BOOT0)") (class "Default")
      (node (ref "R13") (pin "2") (pinfunction "2_2") (pintype "passive"))
      (node (ref "U1") (pin "94") (pinfunction "BOOT0_94") (pintype "input"))
    )
    (net (code "60") (name "Net-(U1-OSC_IN)") (class "Default")
      (node (ref "C10") (pin "2") (pinfunction "2_2") (pintype "passive"))
      (node (ref "U1") (pin "12") (pinfunction "OSC_IN_12") (pintype "input"))
      (node (ref "Y1") (pin "2") (pinfunction "OSC2_2") (pintype "passive"))
    )
    (net (code "61") (name "Net-(U1-OSC_OUT)") (class "Default")
      (node (ref "C11") (pin "2") (pinfunction "2_2") (pintype "passive"))
      (node (ref "U1") (pin "13") (pinfunction "OSC_OUT_13") (pintype "output"))
      (node (ref "Y1") (pin "1") (pinfunction "OSC1_1") (pintype "passive"))
    )
    (net (code "62") (name "Net-(U1-PA11)") (class "Default")
      (node (ref "R10") (pin "2") (pinfunction "2_2") (pintype "passive"))
      (node (ref "U1") (pin "70") (pinfunction "PA11_70") (pintype "bidirectional"))
    )
    (net (code "63") (name "Net-(U1-PA12)") (class "Default")
      (node (ref "R11") (pin "2") (pinfunction "2_2") (pintype "passive"))
      (node (ref "U1") (pin "71") (pinfunction "PA12_71") (pintype "bidirectional"))
    )
    (net (code "64") (name "Net-(U1-PB2{slash}BOOT1)") (class "Default")
      (node (ref "R12") (pin "2") (pinfunction "2_2") (pintype "passive"))
      (node (ref "U1") (pin "37") (pinfunction "PB2/BOOT1_37") (pintype "bidirectional"))
    )
    (net (code "65") (name "Net-(U2-OSCIN)") (class "Default")
      (node (ref "C28") (pin "2") (pinfunction "2_2") (pintype "passive"))
      (node (ref "U2") (pin "21") (pinfunction "OSCIN_21") (pintype "passive"))
      (node (ref "Y2") (pin "2") (pinfunction "OSC2_2") (pintype "passive"))
    )
    (net (code "66") (name "Net-(U2-OSCOUT)") (class "Default")
      (node (ref "C29") (pin "2") (pinfunction "2_2") (pintype "passive"))
      (node (ref "U2") (pin "22") (pinfunction "OSCOUT_22") (pintype "passive"))
      (node (ref "Y2") (pin "1") (pinfunction "OSC1_1") (pintype "passive"))
    )
    (net (code "67") (name "Net-(U2-RX)") (class "Default")
      (node (ref "R20") (pin "1") (pinfunction "1_1") (pintype "passive"))
      (node (ref "R21") (pin "2") (pinfunction "2_2") (pintype "passive"))
      (node (ref "U2") (pin "17") (pinfunction "RX_17") (pintype "passive"))
    )
    (net (code "68") (name "Net-(U3-PORADJ)") (class "Default")
      (node (ref "R81") (pin "1") (pinfunction "1_1") (pintype "passive"))
      (node (ref "R82") (pin "2") (pinfunction "2_2") (pintype "passive"))
      (node (ref "U3") (pin "2") (pinfunction "PORADJ_2") (pintype "passive"))
    )
    (net (code "69") (name "Net-(U3-SAM)") (class "Default")
      (node (ref "C84") (pin "2") (pinfunction "2_2") (pintype "passive"))
      (node (ref "U3") (pin "15") (pinfunction "SAM_15") (pintype "passive"))
    )
    (net (code "70") (name "Net-(U3-SAP)") (class "Default")
      (node (ref "C84") (pin "1") (pinfunction "1_1") (pintype "passive"))
      (node (ref "U3") (pin "20") (pinfunction "SAP_20") (pintype "passive"))
    )
    (net (code "71") (name "Net-(U3-SBM)") (class "Default")
      (node (ref "C86") (pin "2") (pinfunction "2_2") (pintype "passive"))
      (node (ref "U3") (pin "17") (pinfunction "SBM_17") (pintype "passive"))
    )
    (net (code "72") (name "Net-(U3-SBP)") (class "Default")
      (node (ref "C86") (pin "1") (pinfunction "1_1") (pintype "passive"))
      (node (ref "U3") (pin "19") (pinfunction "SBP_19") (pintype "passive"))
    )
    (net (code "73") (name "Net-(U3-VREG)") (class "Default")
      (node (ref "C83") (pin "1") (pinfunction "1_1") (pintype "passive"))
      (node (ref "U3") (pin "14") (pinfunction "VREG_14") (pintype "passive"))
    )
    (net (code "74") (name "Net-(U3-VUP)") (class "Default")
      (node (ref "C85") (pin "2") (pinfunction "2_2") (pintype "passive"))
      (node (ref "U3") (pin "21") (pinfunction "VUP_21") (pintype "passive"))
    )
    (net (code "75") (name "Net-(U3-Vcc)") (class "Default")
      (node (ref "C89") (pin "2") (pinfunction "2_2") (pintype "passive"))
      (node (ref "R83") (pin "1") (pinfunction "1_1") (pintype "passive"))
      (node (ref "U3") (pin "22") (pinfunction "Vcc_22") (pintype "passive"))
    )
    (net (code "76") (name "Net-(U3-XTAL1)") (class "Default")
      (node (ref "C82") (pin "2") (pinfunction "2_2") (pintype "passive"))
      (node (ref "U3") (pin "12") (pinfunction "XTAL1_12") (pintype "passive"))
    )
    (net (code "77") (name "unconnected-(J2-NC-Pad4)") (class "Default")
      (node (ref "J2") (pin "4") (pinfunction "NC_4") (pintype "passive"))
    )
    (net (code "78") (name "unconnected-(J2-NC-Pad6)") (class "Default")
      (node (ref "J2") (pin "6") (pinfunction "NC_6") (pintype "passive"))
    )
    (net (code "79") (name "unconnected-(J2-NC-Pad8)") (class "Default")
      (node (ref "J2") (pin "8") (pinfunction "NC_8") (pintype "passive"))
    )
    (net (code "80") (name "unconnected-(J3-Pad17)") (class "Default")
      (node (ref "J3") (pin "17") (pinfunction "17_17") (pintype "passive"))
    )
    (net (code "81") (name "unconnected-(J3-Pad19)") (class "Default")
      (node (ref "J3") (pin "19") (pinfunction "19_19") (pintype "passive"))
    )
    (net (code "82") (name "unconnected-(P5-Pad3)") (class "Default")
      (node (ref "P5") (pin "3") (pinfunction "3_3") (pintype "passive"))
    )
    (net (code "83") (name "unconnected-(U1-NC-Pad73)") (class "Default")
      (node (ref "U1") (pin "73") (pinfunction "NC_73") (pintype "passive"))
    )
    (net (code "84") (name "unconnected-(U1-PA0-WKUP-Pad23)") (class "Default")
      (node (ref "U1") (pin "23") (pinfunction "PA0-WKUP_23") (pintype "bidirectional"))
    )
    (net (code "85") (name "unconnected-(U1-PA1-Pad24)") (class "Default")
      (node (ref "U1") (pin "24") (pinfunction "PA1_24") (pintype "bidirectional"))
    )
    (net (code "86") (name "unconnected-(U1-PA2-Pad25)") (class "Default")
      (node (ref "U1") (pin "25") (pinfunction "PA2_25") (pintype "bidirectional"))
    )
    (net (code "87") (name "unconnected-(U1-PA3-Pad26)") (class "Default")
      (node (ref "U1") (pin "26") (pinfunction "PA3_26") (pintype "bidirectional"))
    )
    (net (code "88") (name "unconnected-(U1-PA10-Pad69)") (class "Default")
      (node (ref "U1") (pin "69") (pinfunction "PA10_69") (pintype "bidirectional"))
    )
    (net (code "89") (name "unconnected-(U1-PB0-Pad35)") (class "Default")
      (node (ref "U1") (pin "35") (pinfunction "PB0_35") (pintype "bidirectional"))
    )
    (net (code "90") (name "unconnected-(U1-PB1-Pad36)") (class "Default")
      (node (ref "U1") (pin "36") (pinfunction "PB1_36") (pintype "bidirectional"))
    )
    (net (code "91") (name "unconnected-(U1-PB5-Pad91)") (class "Default")
      (node (ref "U1") (pin "91") (pinfunction "PB5_91") (pintype "bidirectional"))
    )
    (net (code "92") (name "unconnected-(U1-PB8-Pad95)") (class "Default")
      (node (ref "U1") (pin "95") (pinfunction "PB8_95") (pintype "bidirectional"))
    )
    (net (code "93") (name "unconnected-(U1-PB9-Pad96)") (class "Default")
      (node (ref "U1") (pin "96") (pinfunction "PB9_96") (pintype "bidirectional"))
    )
    (net (code "94") (name "unconnected-(U1-PB11-Pad48)") (class "Default")
      (node (ref "U1") (pin "48") (pinfunction "PB11_48") (pintype "bidirectional"))
    )
    (net (code "95") (name "unconnected-(U1-PB13-Pad52)") (class "Default")
      (node (ref "U1") (pin "52") (pinfunction "PB13_52") (pintype "bidirectional"))
    )
    (net (code "96") (name "unconnected-(U1-PB14-Pad53)") (class "Default")
      (node (ref "U1") (pin "53") (pinfunction "PB14_53") (pintype "bidirectional"))
    )
    (net (code "97") (name "unconnected-(U1-PB15-Pad54)") (class "Default")
      (node (ref "U1") (pin "54") (pinfunction "PB15_54") (pintype "bidirectional"))
    )
    (net (code "98") (name "unconnected-(U1-PC4-Pad33)") (class "Default")
      (node (ref "U1") (pin "33") (pinfunction "PC4_33") (pintype "bidirectional"))
    )
    (net (code "99") (name "unconnected-(U1-PC5-Pad34)") (class "Default")
      (node (ref "U1") (pin "34") (pinfunction "PC5_34") (pintype "bidirectional"))
    )
    (net (code "100") (name "unconnected-(U1-PC6-Pad63)") (class "Default")
      (node (ref "U1") (pin "63") (pinfunction "PC6_63") (pintype "bidirectional"))
    )
    (net (code "101") (name "unconnected-(U1-PC7-Pad64)") (class "Default")
      (node (ref "U1") (pin "64") (pinfunction "PC7_64") (pintype "bidirectional"))
    )
    (net (code "102") (name "unconnected-(U1-PC9-Pad66)") (class "Default")
      (node (ref "U1") (pin "66") (pinfunction "PC9_66") (pintype "bidirectional"))
    )
    (net (code "103") (name "unconnected-(U1-PC13-TAMPER-RTC-Pad7)") (class "Default")
      (node (ref "U1") (pin "7") (pinfunction "PC13-TAMPER-RTC_7") (pintype "bidirectional"))
    )
    (net (code "104") (name "unconnected-(U1-PC14-OSC32_IN-Pad8)") (class "Default")
      (node (ref "U1") (pin "8") (pinfunction "PC14-OSC32_IN_8") (pintype "bidirectional"))
    )
    (net (code "105") (name "unconnected-(U1-PC15-OSC32_OUT-Pad9)") (class "Default")
      (node (ref "U1") (pin "9") (pinfunction "PC15-OSC32_OUT_9") (pintype "bidirectional"))
    )
    (net (code "106") (name "unconnected-(U1-PD4-Pad85)") (class "Default")
      (node (ref "U1") (pin "85") (pinfunction "PD4_85") (pintype "bidirectional"))
    )
    (net (code "107") (name "unconnected-(U1-PD5-Pad86)") (class "Default")
      (node (ref "U1") (pin "86") (pinfunction "PD5_86") (pintype "bidirectional"))
    )
    (net (code "108") (name "unconnected-(U1-PD6-Pad87)") (class "Default")
      (node (ref "U1") (pin "87") (pinfunction "PD6_87") (pintype "bidirectional"))
    )
    (net (code "109") (name "unconnected-(U1-PD7-Pad88)") (class "Default")
      (node (ref "U1") (pin "88") (pinfunction "PD7_88") (pintype "bidirectional"))
    )
    (net (code "110") (name "unconnected-(U1-PD8-Pad55)") (class "Default")
      (node (ref "U1") (pin "55") (pinfunction "PD8_55") (pintype "bidirectional"))
    )
    (net (code "111") (name "unconnected-(U1-PD9-Pad56)") (class "Default")
      (node (ref "U1") (pin "56") (pinfunction "PD9_56") (pintype "bidirectional"))
    )
    (net (code "112") (name "unconnected-(U1-PD10-Pad57)") (class "Default")
      (node (ref "U1") (pin "57") (pinfunction "PD10_57") (pintype "bidirectional"))
    )
    (net (code "113") (name "unconnected-(U1-PD11-Pad58)") (class "Default")
      (node (ref "U1") (pin "58") (pinfunction "PD11_58") (pintype "bidirectional"))
    )
    (net (code "114") (name "unconnected-(U1-PD12-Pad59)") (class "Default")
      (node (ref "U1") (pin "59") (pinfunction "PD12_59") (pintype "bidirectional"))
    )
    (net (code "115") (name "unconnected-(U1-PD13-Pad60)") (class "Default")
      (node (ref "U1") (pin "60") (pinfunction "PD13_60") (pintype "bidirectional"))
    )
    (net (code "116") (name "unconnected-(U1-PD14-Pad61)") (class "Default")
      (node (ref "U1") (pin "61") (pinfunction "PD14_61") (pintype "bidirectional"))
    )
    (net (code "117") (name "unconnected-(U1-PD15-Pad62)") (class "Default")
      (node (ref "U1") (pin "62") (pinfunction "PD15_62") (pintype "bidirectional"))
    )
    (net (code "118") (name "unconnected-(U1-PE0-Pad97)") (class "Default")
      (node (ref "U1") (pin "97") (pinfunction "PE0_97") (pintype "bidirectional"))
    )
    (net (code "119") (name "unconnected-(U1-PE1-Pad98)") (class "Default")
      (node (ref "U1") (pin "98") (pinfunction "PE1_98") (pintype "bidirectional"))
    )
    (net (code "120") (name "unconnected-(U1-PE2-Pad1)") (class "Default")
      (node (ref "U1") (pin "1") (pinfunction "PE2_1") (pintype "bidirectional"))
    )
    (net (code "121") (name "unconnected-(U1-PE3-Pad2)") (class "Default")
      (node (ref "U1") (pin "2") (pinfunction "PE3_2") (pintype "bidirectional"))
    )
    (net (code "122") (name "unconnected-(U1-PE4-Pad3)") (class "Default")
      (node (ref "U1") (pin "3") (pinfunction "PE4_3") (pintype "bidirectional"))
    )
    (net (code "123") (name "unconnected-(U1-PE5-Pad4)") (class "Default")
      (node (ref "U1") (pin "4") (pinfunction "PE5_4") (pintype "bidirectional"))
    )
    (net (code "124") (name "unconnected-(U1-PE6-Pad5)") (class "Default")
      (node (ref "U1") (pin "5") (pinfunction "PE6_5") (pintype "bidirectional"))
    )
    (net (code "125") (name "unconnected-(U1-PE7-Pad38)") (class "Default")
      (node (ref "U1") (pin "38") (pinfunction "PE7_38") (pintype "bidirectional"))
    )
    (net (code "126") (name "unconnected-(U1-PE8-Pad39)") (class "Default")
      (node (ref "U1") (pin "39") (pinfunction "PE8_39") (pintype "bidirectional"))
    )
    (net (code "127") (name "unconnected-(U1-PE9-Pad40)") (class "Default")
      (node (ref "U1") (pin "40") (pinfunction "PE9_40") (pintype "bidirectional"))
    )
    (net (code "128") (name "unconnected-(U1-PE10-Pad41)") (class "Default")
      (node (ref "U1") (pin "41") (pinfunction "PE10_41") (pintype "bidirectional"))
    )
    (net (code "129") (name "unconnected-(U1-PE11-Pad42)") (class "Default")
      (node (ref "U1") (pin "42") (pinfunction "PE11_42") (pintype "bidirectional"))
    )
    (net (code "130") (name "unconnected-(U1-PE12-Pad43)") (class "Default")
      (node (ref "U1") (pin "43") (pinfunction "PE12_43") (pintype "bidirectional"))
    )
    (net (code "131") (name "unconnected-(U1-PE13-Pad44)") (class "Default")
      (node (ref "U1") (pin "44") (pinfunction "PE13_44") (pintype "bidirectional"))
    )
    (net (code "132") (name "unconnected-(U1-PE14-Pad45)") (class "Default")
      (node (ref "U1") (pin "45") (pinfunction "PE14_45") (pintype "bidirectional"))
    )
    (net (code "133") (name "unconnected-(U1-PE15-Pad46)") (class "Default")
      (node (ref "U1") (pin "46") (pinfunction "PE15_46") (pintype "bidirectional"))
    )
    (net (code "134") (name "unconnected-(U1-VBAT-Pad6)") (class "Default")
      (node (ref "U1") (pin "6") (pinfunction "VBAT_6") (pintype "power_in"))
    )
    (net (code "135") (name "unconnected-(U1-VREF+-Pad21)") (class "Default")
      (node (ref "U1") (pin "21") (pinfunction "VREF+_21") (pintype "power_in"))
    )
    (net (code "136") (name "unconnected-(U1-VREF--Pad20)") (class "Default")
      (node (ref "U1") (pin "20") (pinfunction "VREF-_20") (pintype "power_in"))
    )
    (net (code "137") (name "unconnected-(U2-D1-Pad25)") (class "Default")
      (node (ref "U2") (pin "25") (pinfunction "D1_25") (pintype "passive"))
    )
    (net (code "138") (name "unconnected-(U2-D2-Pad26)") (class "Default")
      (node (ref "U2") (pin "26") (pinfunction "D2_26") (pintype "passive"))
    )
    (net (code "139") (name "unconnected-(U2-D3-Pad27)") (class "Default")
      (node (ref "U2") (pin "27") (pinfunction "D3_27") (pintype "passive"))
    )
    (net (code "140") (name "unconnected-(U2-D4-Pad28)") (class "Default")
      (node (ref "U2") (pin "28") (pinfunction "D4_28") (pintype "passive"))
    )
    (net (code "141") (name "unconnected-(U2-SVDD-Pad9)") (class "Default")
      (node (ref "U2") (pin "9") (pinfunction "SVDD_9") (pintype "passive"))
    )
    (net (code "142") (name "unconnected-(U3-AUX1-Pad26)") (class "Default")
      (node (ref "U3") (pin "26") (pinfunction "AUX1_26") (pintype "passive"))
    )
    (net (code "143") (name "unconnected-(U3-AUX1UC-Pad31)") (class "Default")
      (node (ref "U3") (pin "31") (pinfunction "AUX1UC_31") (pintype "passive"))
    )
    (net (code "144") (name "unconnected-(U3-AUX2-Pad27)") (class "Default")
      (node (ref "U3") (pin "27") (pinfunction "AUX2_27") (pintype "passive"))
    )
    (net (code "145") (name "unconnected-(U3-AUX2UC-Pad32)") (class "Default")
      (node (ref "U3") (pin "32") (pinfunction "AUX2UC_32") (pintype "passive"))
    )
    (net (code "146") (name "unconnected-(U3-XTAL2-Pad13)") (class "Default")
      (node (ref "U3") (pin "13") (pinfunction "XTAL2_13") (pintype "passive"))
    )
  )
)
